# PT4115_Breakout.net
KiCad netlist of a schematic drawn in EAGLE
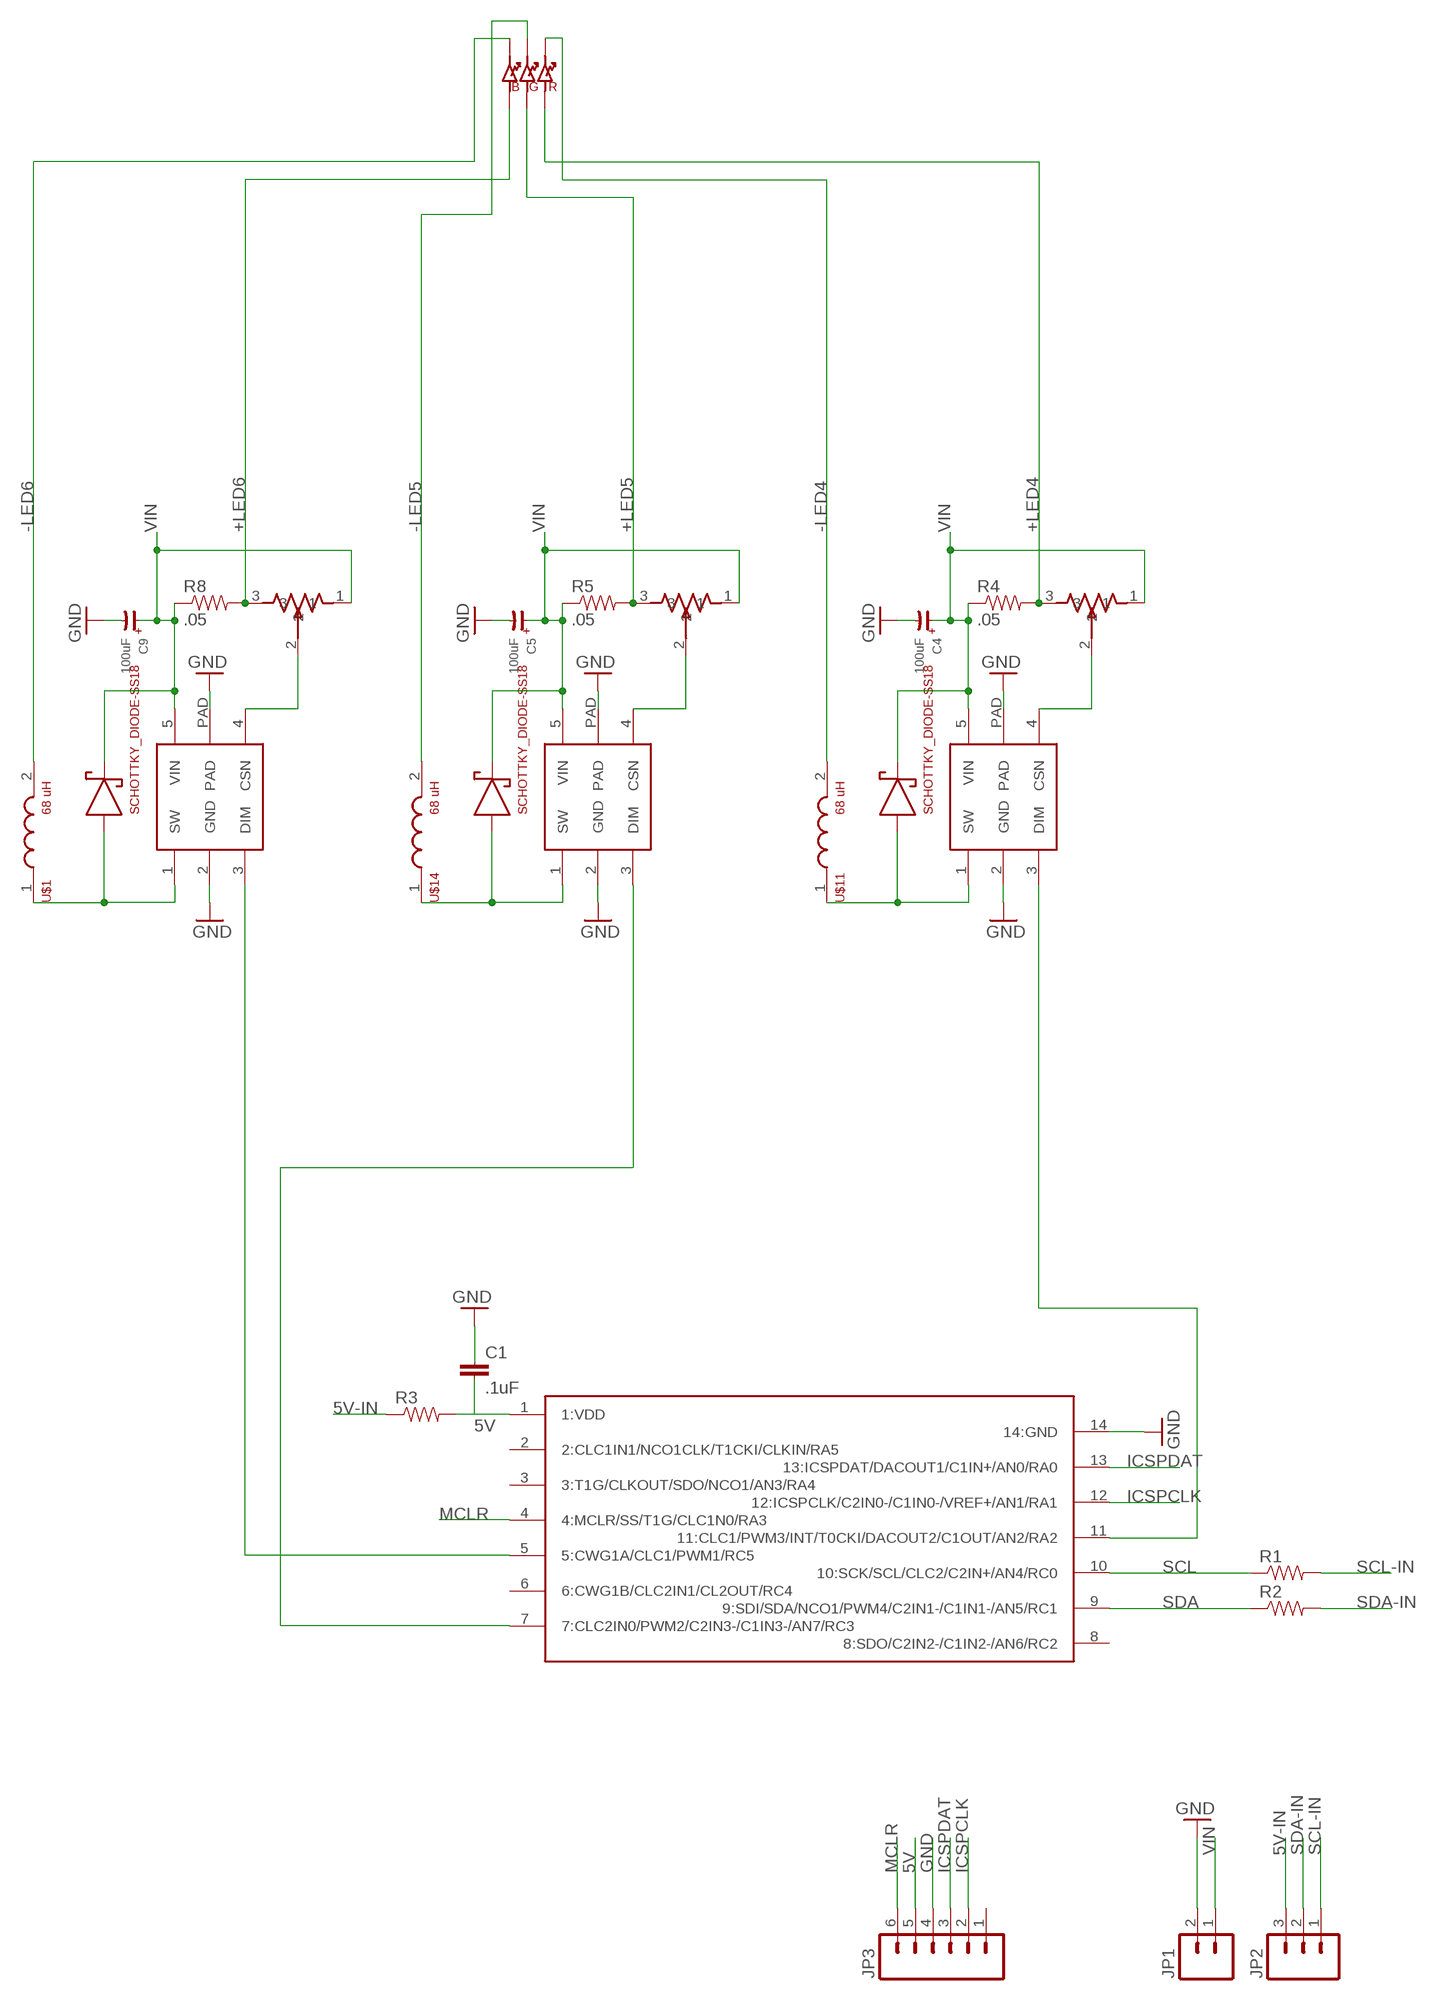
[diagram p0: schematic, sheet 1]

(export (version "E")
  (design (tool "Eeschema 10.0.6"))
  (components
    (comp (ref "C1")
      (value ".1uF")
      (footprint "eagle-import:0805")
      (libsource (lib "eagle-import") (part "CAP0805"))
    )
    (comp (ref "C4")
      (value "100uF")
      (footprint "eagle-import:8MMCAP")
      (libsource (lib "eagle-import") (part "CAPPOL-8X11"))
    )
    (comp (ref "C5")
      (value "100uF")
      (footprint "eagle-import:8MMCAP")
      (libsource (lib "eagle-import") (part "CAPPOL-8X11"))
    )
    (comp (ref "C9")
      (value "100uF")
      (footprint "eagle-import:8MMCAP")
      (libsource (lib "eagle-import") (part "CAPPOL-8X11"))
    )
    (comp (ref "JP1")
      (value "M02LOCK")
      (footprint "eagle-import:1X02_LOCK")
      (libsource (lib "eagle-import") (part "M02LOCK"))
    )
    (comp (ref "JP2")
      (value "M03LOCK")
      (footprint "eagle-import:1X03_LOCK")
      (libsource (lib "eagle-import") (part "M03LOCK"))
    )
    (comp (ref "JP3")
      (value "M06LOCK")
      (footprint "eagle-import:1X06_LOCK")
      (libsource (lib "eagle-import") (part "M06LOCK"))
    )
    (comp (ref "R1")
      (value "RESISTOR")
      (footprint "eagle-import:0805")
      (libsource (lib "eagle-import") (part "RESISTOR"))
    )
    (comp (ref "R2")
      (value "RESISTOR")
      (footprint "eagle-import:0805")
      (libsource (lib "eagle-import") (part "RESISTOR"))
    )
    (comp (ref "R3")
      (value "RESISTOR")
      (footprint "eagle-import:0805")
      (libsource (lib "eagle-import") (part "RESISTOR"))
    )
    (comp (ref "R4")
      (value ".05")
      (footprint "eagle-import:1206")
      (libsource (lib "eagle-import") (part "RESISTOR1206"))
    )
    (comp (ref "R5")
      (value ".05")
      (footprint "eagle-import:1206")
      (libsource (lib "eagle-import") (part "RESISTOR1206"))
    )
    (comp (ref "R8")
      (value ".05")
      (footprint "eagle-import:1206")
      (libsource (lib "eagle-import") (part "RESISTOR1206"))
    )
    (comp (ref "U$1")
      (value "68 uH")
      (footprint "eagle-import:VLF10040")
      (libsource (lib "eagle-import") (part "INDUCTORVLF10040"))
    )
    (comp (ref "U$4")
      (value "BIGRGB")
      (footprint "eagle-import:BIGRGB")
      (libsource (lib "eagle-import") (part "BIGRGB"))
    )
    (comp (ref "U$5")
      (value "PIC16F1503TSSOP14")
      (footprint "eagle-import:TSSOP14")
      (libsource (lib "eagle-import") (part "PIC16F1503TSSOP14"))
    )
    (comp (ref "U$8")
      (value "TRIMPOTTC33X-2")
      (footprint "eagle-import:TC33X-2")
      (libsource (lib "eagle-import") (part "TRIMPOTTC33X-2"))
    )
    (comp (ref "U$9")
      (value "TRIMPOTTC33X-2")
      (footprint "eagle-import:TC33X-2")
      (libsource (lib "eagle-import") (part "TRIMPOTTC33X-2"))
    )
    (comp (ref "U$10")
      (value "TRIMPOTTC33X-2")
      (footprint "eagle-import:TC33X-2")
      (libsource (lib "eagle-import") (part "TRIMPOTTC33X-2"))
    )
    (comp (ref "U$11")
      (value "68 uH")
      (footprint "eagle-import:VLF10040")
      (libsource (lib "eagle-import") (part "INDUCTORVLF10040"))
    )
    (comp (ref "U$12")
      (value "SCHOTTKY_DIODE-SS18")
      (footprint "eagle-import:DO-214")
      (libsource (lib "eagle-import") (part "SCHOTTKY_DIODE-SS18"))
    )
    (comp (ref "U$13")
      (value "PT4115")
      (footprint "eagle-import:SOT89-5")
      (libsource (lib "eagle-import") (part "PT4115"))
    )
    (comp (ref "U$14")
      (value "68 uH")
      (footprint "eagle-import:VLF10040")
      (libsource (lib "eagle-import") (part "INDUCTORVLF10040"))
    )
    (comp (ref "U$15")
      (value "SCHOTTKY_DIODE-SS18")
      (footprint "eagle-import:DO-214")
      (libsource (lib "eagle-import") (part "SCHOTTKY_DIODE-SS18"))
    )
    (comp (ref "U$16")
      (value "PT4115")
      (footprint "eagle-import:SOT89-5")
      (libsource (lib "eagle-import") (part "PT4115"))
    )
    (comp (ref "U$23")
      (value "SCHOTTKY_DIODE-SS18")
      (footprint "eagle-import:DO-214")
      (libsource (lib "eagle-import") (part "SCHOTTKY_DIODE-SS18"))
    )
    (comp (ref "U$24")
      (value "PT4115")
      (footprint "eagle-import:SOT89-5")
      (libsource (lib "eagle-import") (part "PT4115"))
    )
  )
  (nets
    (net (code "1") (name "/+LED4") (class "Default")
      (node (ref "R4") (pin "2") (pinfunction "2_2") (pintype "passive"))
      (node (ref "U$10") (pin "3") (pinfunction "3_3") (pintype "bidirectional"))
      (node (ref "U$4") (pin "R+") (pinfunction "R+_R+") (pintype "bidirectional"))
    )
    (net (code "2") (name "/+LED5") (class "Default")
      (node (ref "R5") (pin "2") (pinfunction "2_2") (pintype "passive"))
      (node (ref "U$4") (pin "G+") (pinfunction "G+_G+") (pintype "bidirectional"))
      (node (ref "U$9") (pin "3") (pinfunction "3_3") (pintype "bidirectional"))
    )
    (net (code "3") (name "/+LED6") (class "Default")
      (node (ref "R8") (pin "2") (pinfunction "2_2") (pintype "passive"))
      (node (ref "U$4") (pin "B+") (pinfunction "B+_B+") (pintype "bidirectional"))
      (node (ref "U$8") (pin "3") (pinfunction "3_3") (pintype "bidirectional"))
    )
    (net (code "4") (name "/-LED4") (class "Default")
      (node (ref "U$11") (pin "2") (pinfunction "P$2_2") (pintype "bidirectional"))
      (node (ref "U$4") (pin "R-") (pinfunction "R-_R-") (pintype "bidirectional"))
    )
    (net (code "5") (name "/-LED5") (class "Default")
      (node (ref "U$14") (pin "2") (pinfunction "P$2_2") (pintype "bidirectional"))
      (node (ref "U$4") (pin "G-") (pinfunction "G-_G-") (pintype "bidirectional"))
    )
    (net (code "6") (name "/-LED6") (class "Default")
      (node (ref "U$1") (pin "2") (pinfunction "P$2_2") (pintype "bidirectional"))
      (node (ref "U$4") (pin "B-") (pinfunction "B-_B-") (pintype "bidirectional"))
    )
    (net (code "7") (name "/5V") (class "Default")
      (node (ref "C1") (pin "2") (pinfunction "2_2") (pintype "passive"))
      (node (ref "JP3") (pin "5") (pinfunction "5_5") (pintype "passive"))
      (node (ref "R3") (pin "2") (pinfunction "2_2") (pintype "passive"))
      (node (ref "U$5") (pin "1") (pinfunction "1:VDD_1") (pintype "bidirectional"))
    )
    (net (code "8") (name "/5V-IN") (class "Default")
      (node (ref "JP2") (pin "3") (pinfunction "3_3") (pintype "passive"))
      (node (ref "R3") (pin "1") (pinfunction "1_1") (pintype "passive"))
    )
    (net (code "9") (name "/ICSPCLK") (class "Default")
      (node (ref "JP3") (pin "2") (pinfunction "2_2") (pintype "passive"))
      (node (ref "U$5") (pin "12") (pinfunction "12:ICSPCLK/C2IN0-/C1IN0-/VREF+/AN1/RA1_12") (pintype "bidirectional"))
    )
    (net (code "10") (name "/ICSPDAT") (class "Default")
      (node (ref "JP3") (pin "3") (pinfunction "3_3") (pintype "passive"))
      (node (ref "U$5") (pin "13") (pinfunction "13:ICSPDAT/DACOUT1/C1IN+/AN0/RA0_13") (pintype "bidirectional"))
    )
    (net (code "11") (name "/MCLR") (class "Default")
      (node (ref "JP3") (pin "6") (pinfunction "6_6") (pintype "passive"))
      (node (ref "U$5") (pin "4") (pinfunction "4:MCLR/SS/T1G/CLC1N0/RA3_4") (pintype "bidirectional"))
    )
    (net (code "12") (name "/SCL") (class "Default")
      (node (ref "R1") (pin "1") (pinfunction "1_1") (pintype "passive"))
      (node (ref "U$5") (pin "10") (pinfunction "10:SCK/SCL/CLC2/C2IN+/AN4/RC0_10") (pintype "bidirectional"))
    )
    (net (code "13") (name "/SCL-IN") (class "Default")
      (node (ref "JP2") (pin "1") (pinfunction "1_1") (pintype "passive"))
      (node (ref "R1") (pin "2") (pinfunction "2_2") (pintype "passive"))
    )
    (net (code "14") (name "/SDA") (class "Default")
      (node (ref "R2") (pin "1") (pinfunction "1_1") (pintype "passive"))
      (node (ref "U$5") (pin "9") (pinfunction "9:SDI/SDA/NCO1/PWM4/C2IN1-/C1IN1-/AN5/RC1_9") (pintype "bidirectional"))
    )
    (net (code "15") (name "/SDA-IN") (class "Default")
      (node (ref "JP2") (pin "2") (pinfunction "2_2") (pintype "passive"))
      (node (ref "R2") (pin "2") (pinfunction "2_2") (pintype "passive"))
    )
    (net (code "16") (name "/VIN") (class "Default")
      (node (ref "C4") (pin "+") (pinfunction "+_+") (pintype "bidirectional"))
      (node (ref "C5") (pin "+") (pinfunction "+_+") (pintype "bidirectional"))
      (node (ref "C9") (pin "+") (pinfunction "+_+") (pintype "bidirectional"))
      (node (ref "JP1") (pin "1") (pinfunction "1_1") (pintype "passive"))
      (node (ref "R4") (pin "1") (pinfunction "1_1") (pintype "passive"))
      (node (ref "R5") (pin "1") (pinfunction "1_1") (pintype "passive"))
      (node (ref "R8") (pin "1") (pinfunction "1_1") (pintype "passive"))
      (node (ref "U$10") (pin "1") (pinfunction "1_1") (pintype "bidirectional"))
      (node (ref "U$12") (pin "P$1") (pinfunction "CATHODE_P$1") (pintype "bidirectional"))
      (node (ref "U$13") (pin "5") (pinfunction "VIN_5") (pintype "bidirectional"))
      (node (ref "U$15") (pin "P$1") (pinfunction "CATHODE_P$1") (pintype "bidirectional"))
      (node (ref "U$16") (pin "5") (pinfunction "VIN_5") (pintype "bidirectional"))
      (node (ref "U$23") (pin "P$1") (pinfunction "CATHODE_P$1") (pintype "bidirectional"))
      (node (ref "U$24") (pin "5") (pinfunction "VIN_5") (pintype "bidirectional"))
      (node (ref "U$8") (pin "1") (pinfunction "1_1") (pintype "bidirectional"))
      (node (ref "U$9") (pin "1") (pinfunction "1_1") (pintype "bidirectional"))
    )
    (net (code "17") (name "GND") (class "Default")
      (node (ref "C1") (pin "1") (pinfunction "1_1") (pintype "passive"))
      (node (ref "C4") (pin "-") (pinfunction "-_-") (pintype "bidirectional"))
      (node (ref "C5") (pin "-") (pinfunction "-_-") (pintype "bidirectional"))
      (node (ref "C9") (pin "-") (pinfunction "-_-") (pintype "bidirectional"))
      (node (ref "JP1") (pin "2") (pinfunction "2_2") (pintype "passive"))
      (node (ref "JP3") (pin "4") (pinfunction "4_4") (pintype "passive"))
      (node (ref "U$13") (pin "2") (pinfunction "GND_2") (pintype "bidirectional"))
      (node (ref "U$13") (pin "PAD") (pinfunction "PAD_PAD") (pintype "bidirectional"))
      (node (ref "U$16") (pin "2") (pinfunction "GND_2") (pintype "bidirectional"))
      (node (ref "U$16") (pin "PAD") (pinfunction "PAD_PAD") (pintype "bidirectional"))
      (node (ref "U$24") (pin "2") (pinfunction "GND_2") (pintype "bidirectional"))
      (node (ref "U$24") (pin "PAD") (pinfunction "PAD_PAD") (pintype "bidirectional"))
      (node (ref "U$5") (pin "14") (pinfunction "14:GND_14") (pintype "bidirectional"))
    )
    (net (code "18") (name "Net-(U$1-P$1)") (class "Default")
      (node (ref "U$1") (pin "1") (pinfunction "P$1_1") (pintype "bidirectional"))
      (node (ref "U$23") (pin "P$2") (pinfunction "ANODE_P$2") (pintype "bidirectional"))
      (node (ref "U$24") (pin "1") (pinfunction "SW_1") (pintype "bidirectional"))
    )
    (net (code "19") (name "Net-(U$11-P$1)") (class "Default")
      (node (ref "U$11") (pin "1") (pinfunction "P$1_1") (pintype "bidirectional"))
      (node (ref "U$12") (pin "P$2") (pinfunction "ANODE_P$2") (pintype "bidirectional"))
      (node (ref "U$13") (pin "1") (pinfunction "SW_1") (pintype "bidirectional"))
    )
    (net (code "20") (name "Net-(U$13-CSN)") (class "Default")
      (node (ref "U$10") (pin "2") (pinfunction "2_2") (pintype "bidirectional"))
      (node (ref "U$13") (pin "4") (pinfunction "CSN_4") (pintype "bidirectional"))
    )
    (net (code "21") (name "Net-(U$13-DIM)") (class "Default")
      (node (ref "U$13") (pin "3") (pinfunction "DIM_3") (pintype "bidirectional"))
      (node (ref "U$5") (pin "11") (pinfunction "11:CLC1/PWM3/INT/T0CKI/DACOUT2/C1OUT/AN2/RA2_11") (pintype "bidirectional"))
    )
    (net (code "22") (name "Net-(U$14-P$1)") (class "Default")
      (node (ref "U$14") (pin "1") (pinfunction "P$1_1") (pintype "bidirectional"))
      (node (ref "U$15") (pin "P$2") (pinfunction "ANODE_P$2") (pintype "bidirectional"))
      (node (ref "U$16") (pin "1") (pinfunction "SW_1") (pintype "bidirectional"))
    )
    (net (code "23") (name "Net-(U$16-CSN)") (class "Default")
      (node (ref "U$16") (pin "4") (pinfunction "CSN_4") (pintype "bidirectional"))
      (node (ref "U$9") (pin "2") (pinfunction "2_2") (pintype "bidirectional"))
    )
    (net (code "24") (name "Net-(U$16-DIM)") (class "Default")
      (node (ref "U$16") (pin "3") (pinfunction "DIM_3") (pintype "bidirectional"))
      (node (ref "U$5") (pin "7") (pinfunction "7:CLC2IN0/PWM2/C2IN3-/C1IN3-/AN7/RC3_7") (pintype "bidirectional"))
    )
    (net (code "25") (name "Net-(U$24-CSN)") (class "Default")
      (node (ref "U$24") (pin "4") (pinfunction "CSN_4") (pintype "bidirectional"))
      (node (ref "U$8") (pin "2") (pinfunction "2_2") (pintype "bidirectional"))
    )
    (net (code "26") (name "Net-(U$24-DIM)") (class "Default")
      (node (ref "U$24") (pin "3") (pinfunction "DIM_3") (pintype "bidirectional"))
      (node (ref "U$5") (pin "5") (pinfunction "5:CWG1A/CLC1/PWM1/RC5_5") (pintype "bidirectional"))
    )
    (net (code "27") (name "unconnected-(JP3-Pad1)") (class "Default")
      (node (ref "JP3") (pin "1") (pinfunction "1_1") (pintype "passive"))
    )
    (net (code "28") (name "unconnected-(U$5-2:CLC1IN1{slash}NCO1CLK{slash}T1CKI{slash}CLKIN{slash}RA5-Pad2)") (class "Default")
      (node (ref "U$5") (pin "2") (pinfunction "2:CLC1IN1/NCO1CLK/T1CKI/CLKIN/RA5_2") (pintype "bidirectional"))
    )
    (net (code "29") (name "unconnected-(U$5-3:T1G{slash}CLKOUT{slash}SDO{slash}NCO1{slash}AN3{slash}RA4-Pad3)") (class "Default")
      (node (ref "U$5") (pin "3") (pinfunction "3:T1G/CLKOUT/SDO/NCO1/AN3/RA4_3") (pintype "bidirectional"))
    )
    (net (code "30") (name "unconnected-(U$5-6:CWG1B{slash}CLC2IN1{slash}CL2OUT{slash}RC4-Pad6)") (class "Default")
      (node (ref "U$5") (pin "6") (pinfunction "6:CWG1B/CLC2IN1/CL2OUT/RC4_6") (pintype "bidirectional"))
    )
    (net (code "31") (name "unconnected-(U$5-8:SDO{slash}C2IN2-{slash}C1IN2-{slash}AN6{slash}RC2-Pad8)") (class "Default")
      (node (ref "U$5") (pin "8") (pinfunction "8:SDO/C2IN2-/C1IN2-/AN6/RC2_8") (pintype "bidirectional"))
    )
  )
)
